# Measure.net
KiCad netlist of a schematic drawn in Altium Designer
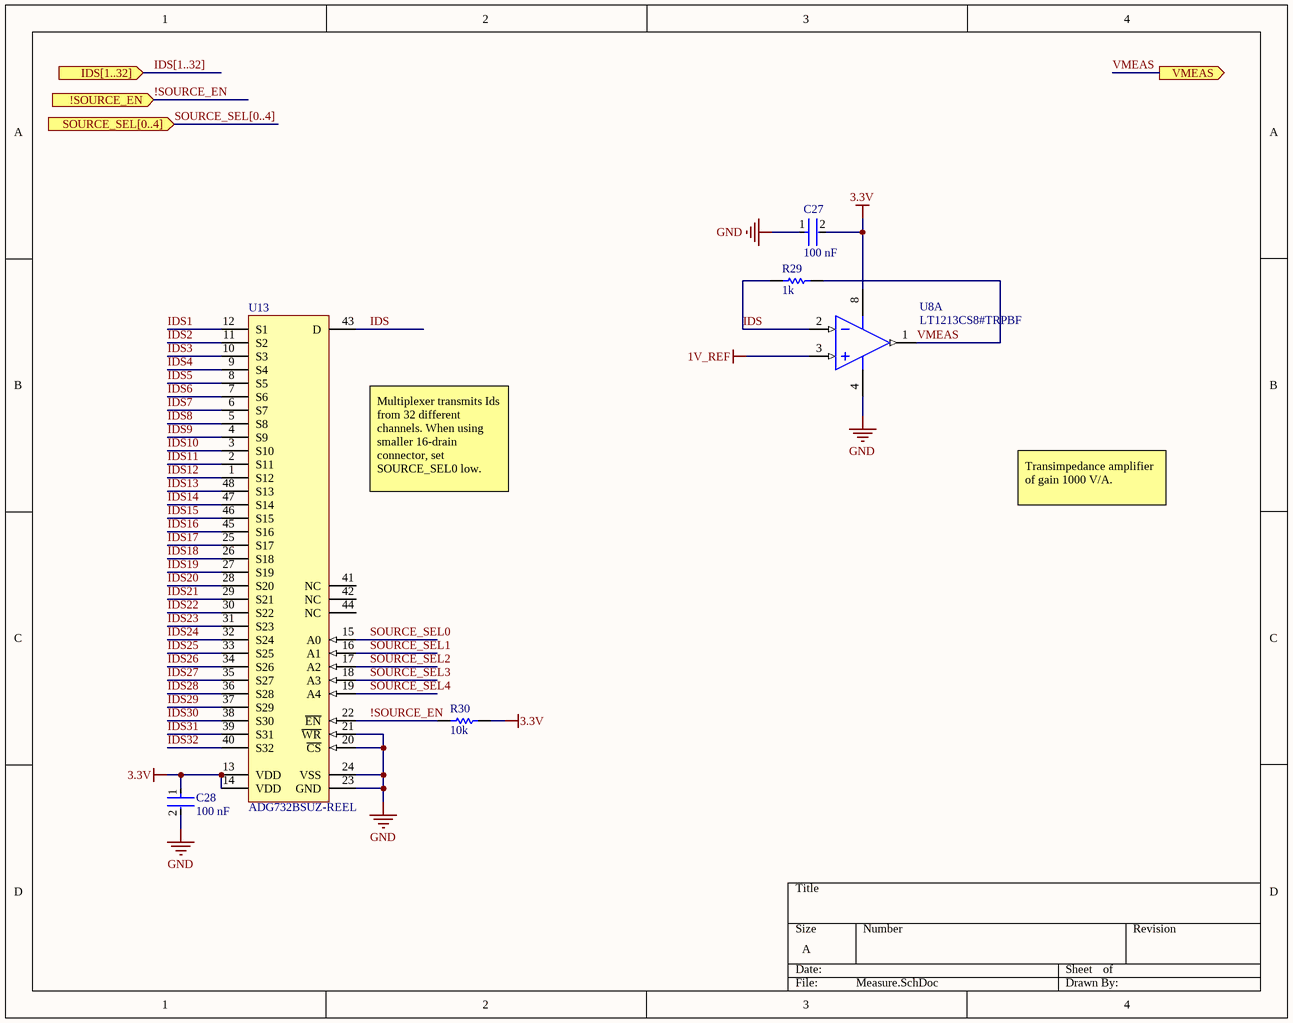
[diagram p0: Measure.SchDoc]

(export (version "E")
  (design (tool "Eeschema 10.0.6"))
  (components
    (comp (ref "C27")
      (value "100 nF")
      (footprint "FP-C0805C-DN-MFG")
      (description "CAP CER 0.1UF 50V X7R 0805")
      (fields
        (field (name "MANUFACTURER PART NUMBER") "C0805C104K5RACTU")
        (field (name "MANUFACTURER") "KEMET")
      )
      (libsource (lib "Altium Content Vault") (part "b4654b650e69147ec39a6b967a45e02"))
    )
    (comp (ref "C28")
      (value "100 nF")
      (footprint "FP-C0805C-DN-MFG")
      (description "CAP CER 0.1UF 50V X7R 0805")
      (fields
        (field (name "MANUFACTURER PART NUMBER") "C0805C104K5RACTU")
        (field (name "MANUFACTURER") "KEMET")
      )
      (libsource (lib "Altium Content Vault") (part "b4654b650e69147ec39a6b967a45e02"))
    )
    (comp (ref "R29")
      (value "1k")
      (footprint "RESC2013X55X40LL15T20")
      (description "TNPW08051K00BEEN")
      (fields (field (name "MANUFACTURER") "Vishay Dale"))
      (libsource (lib "Altium Content Vault") (part "RES"))
    )
    (comp (ref "R30")
      (value "10k")
      (footprint "RESC2013X60X35NL10T20")
      (description "Chip Resistor, 10 KOhm, +/- 1%, 0.125 W, -55 to 155 degC, 0805 (2012 Metric), RoHS, Tape and Reel")
      (fields (field (name "MANUFACTURER") "Yageo"))
      (libsource (lib "Altium Content Vault") (part "RES-2"))
    )
    (comp (ref "U8")
      (value "LT1213CS8#TRPBF")
      (footprint "LT-S8-8_N")
      (fields
        (field (name "LINEAR TECHNOLOGY PART NUMBER") "LT1213")
        (field (name "MANUFACTURER") "Linear Technology")
      )
      (libsource (lib "Altium Content Vault") (part "LT-LT1364-LT18XX-8"))
    )
    (comp (ref "U13")
      (value "ADG732BSUZ-REEL")
      (footprint "ADI-SU-48_N")
      (fields (field (name "MANUFACTURER") "Analog Devices"))
      (libsource (lib "Altium Content Vault") (part "ADI-ADG732-SU-48"))
    )
  )
  (nets
    (net (code "1") (name "/!SOURCE_EN") (class "Default")
      (node (ref "R30") (pin "2") (pinfunction "2_2") (pintype "passive"))
      (node (ref "U13") (pin "22") (pinfunction "~{EN}_22") (pintype "input"))
    )
    (net (code "2") (name "/IDS") (class "Default")
      (node (ref "R29") (pin "1") (pinfunction "1_1") (pintype "passive"))
      (node (ref "U13") (pin "43") (pinfunction "D_43") (pintype "passive"))
      (node (ref "U8") (pin "2") (pinfunction "-IN_A_2") (pintype "input"))
    )
    (net (code "3") (name "/IDS1") (class "Default")
      (node (ref "U13") (pin "12") (pinfunction "S1_12") (pintype "passive"))
    )
    (net (code "4") (name "/IDS2") (class "Default")
      (node (ref "U13") (pin "11") (pinfunction "S2_11") (pintype "passive"))
    )
    (net (code "5") (name "/IDS3") (class "Default")
      (node (ref "U13") (pin "10") (pinfunction "S3_10") (pintype "passive"))
    )
    (net (code "6") (name "/IDS4") (class "Default")
      (node (ref "U13") (pin "9") (pinfunction "S4_9") (pintype "passive"))
    )
    (net (code "7") (name "/IDS5") (class "Default")
      (node (ref "U13") (pin "8") (pinfunction "S5_8") (pintype "passive"))
    )
    (net (code "8") (name "/IDS6") (class "Default")
      (node (ref "U13") (pin "7") (pinfunction "S6_7") (pintype "passive"))
    )
    (net (code "9") (name "/IDS7") (class "Default")
      (node (ref "U13") (pin "6") (pinfunction "S7_6") (pintype "passive"))
    )
    (net (code "10") (name "/IDS8") (class "Default")
      (node (ref "U13") (pin "5") (pinfunction "S8_5") (pintype "passive"))
    )
    (net (code "11") (name "/IDS9") (class "Default")
      (node (ref "U13") (pin "4") (pinfunction "S9_4") (pintype "passive"))
    )
    (net (code "12") (name "/IDS10") (class "Default")
      (node (ref "U13") (pin "3") (pinfunction "S10_3") (pintype "passive"))
    )
    (net (code "13") (name "/IDS11") (class "Default")
      (node (ref "U13") (pin "2") (pinfunction "S11_2") (pintype "passive"))
    )
    (net (code "14") (name "/IDS12") (class "Default")
      (node (ref "U13") (pin "1") (pinfunction "S12_1") (pintype "passive"))
    )
    (net (code "15") (name "/IDS13") (class "Default")
      (node (ref "U13") (pin "48") (pinfunction "S13_48") (pintype "passive"))
    )
    (net (code "16") (name "/IDS14") (class "Default")
      (node (ref "U13") (pin "47") (pinfunction "S14_47") (pintype "passive"))
    )
    (net (code "17") (name "/IDS15") (class "Default")
      (node (ref "U13") (pin "46") (pinfunction "S15_46") (pintype "passive"))
    )
    (net (code "18") (name "/IDS16") (class "Default")
      (node (ref "U13") (pin "45") (pinfunction "S16_45") (pintype "passive"))
    )
    (net (code "19") (name "/IDS17") (class "Default")
      (node (ref "U13") (pin "25") (pinfunction "S17_25") (pintype "passive"))
    )
    (net (code "20") (name "/IDS18") (class "Default")
      (node (ref "U13") (pin "26") (pinfunction "S18_26") (pintype "passive"))
    )
    (net (code "21") (name "/IDS19") (class "Default")
      (node (ref "U13") (pin "27") (pinfunction "S19_27") (pintype "passive"))
    )
    (net (code "22") (name "/IDS20") (class "Default")
      (node (ref "U13") (pin "28") (pinfunction "S20_28") (pintype "passive"))
    )
    (net (code "23") (name "/IDS21") (class "Default")
      (node (ref "U13") (pin "29") (pinfunction "S21_29") (pintype "passive"))
    )
    (net (code "24") (name "/IDS22") (class "Default")
      (node (ref "U13") (pin "30") (pinfunction "S22_30") (pintype "passive"))
    )
    (net (code "25") (name "/IDS23") (class "Default")
      (node (ref "U13") (pin "31") (pinfunction "S23_31") (pintype "passive"))
    )
    (net (code "26") (name "/IDS24") (class "Default")
      (node (ref "U13") (pin "32") (pinfunction "S24_32") (pintype "passive"))
    )
    (net (code "27") (name "/IDS25") (class "Default")
      (node (ref "U13") (pin "33") (pinfunction "S25_33") (pintype "passive"))
    )
    (net (code "28") (name "/IDS26") (class "Default")
      (node (ref "U13") (pin "34") (pinfunction "S26_34") (pintype "passive"))
    )
    (net (code "29") (name "/IDS27") (class "Default")
      (node (ref "U13") (pin "35") (pinfunction "S27_35") (pintype "passive"))
    )
    (net (code "30") (name "/IDS28") (class "Default")
      (node (ref "U13") (pin "36") (pinfunction "S28_36") (pintype "passive"))
    )
    (net (code "31") (name "/IDS29") (class "Default")
      (node (ref "U13") (pin "37") (pinfunction "S29_37") (pintype "passive"))
    )
    (net (code "32") (name "/IDS30") (class "Default")
      (node (ref "U13") (pin "38") (pinfunction "S30_38") (pintype "passive"))
    )
    (net (code "33") (name "/IDS31") (class "Default")
      (node (ref "U13") (pin "39") (pinfunction "S31_39") (pintype "passive"))
    )
    (net (code "34") (name "/IDS32") (class "Default")
      (node (ref "U13") (pin "40") (pinfunction "S32_40") (pintype "passive"))
    )
    (net (code "36") (name "/SOURCE_SEL0") (class "Default")
      (node (ref "U13") (pin "15") (pinfunction "A0_15") (pintype "input"))
    )
    (net (code "37") (name "/SOURCE_SEL1") (class "Default")
      (node (ref "U13") (pin "16") (pinfunction "A1_16") (pintype "input"))
    )
    (net (code "38") (name "/SOURCE_SEL2") (class "Default")
      (node (ref "U13") (pin "17") (pinfunction "A2_17") (pintype "input"))
    )
    (net (code "39") (name "/SOURCE_SEL3") (class "Default")
      (node (ref "U13") (pin "18") (pinfunction "A3_18") (pintype "input"))
    )
    (net (code "40") (name "/SOURCE_SEL4") (class "Default")
      (node (ref "U13") (pin "19") (pinfunction "A4_19") (pintype "input"))
    )
    (net (code "42") (name "/VMEAS") (class "Default")
      (node (ref "R29") (pin "2") (pinfunction "2_2") (pintype "passive"))
      (node (ref "U8") (pin "1") (pinfunction "OUT_A_1") (pintype "output"))
    )
    (net (code "43") (name "1V_REF") (class "Default")
      (node (ref "U8") (pin "3") (pinfunction "+IN_A_3") (pintype "input"))
    )
    (net (code "44") (name "3.3V") (class "Default")
      (node (ref "C27") (pin "2") (pinfunction "2_2") (pintype "passive"))
      (node (ref "C28") (pin "1") (pinfunction "1_1") (pintype "passive"))
      (node (ref "R30") (pin "1") (pinfunction "1_1") (pintype "passive"))
      (node (ref "U13") (pin "13") (pinfunction "VDD_13") (pintype "power_in"))
      (node (ref "U13") (pin "14") (pinfunction "VDD_14") (pintype "power_in"))
      (node (ref "U8") (pin "8") (pinfunction "V+_8") (pintype "power_in"))
    )
    (net (code "45") (name "GND") (class "Default")
      (node (ref "C27") (pin "1") (pinfunction "1_1") (pintype "passive"))
      (node (ref "C28") (pin "2") (pinfunction "2_2") (pintype "passive"))
      (node (ref "U13") (pin "20") (pinfunction "~{CS}_20") (pintype "input"))
      (node (ref "U13") (pin "21") (pinfunction "~{WR}_21") (pintype "input"))
      (node (ref "U13") (pin "23") (pinfunction "GND_23") (pintype "power_in"))
      (node (ref "U13") (pin "24") (pinfunction "VSS_24") (pintype "power_in"))
      (node (ref "U8") (pin "4") (pinfunction "V-_4") (pintype "power_in"))
    )
    (net (code "46") (name "unconnected-(U13-NC-Pad41)") (class "Default")
      (node (ref "U13") (pin "41") (pinfunction "NC_41") (pintype "passive"))
    )
    (net (code "47") (name "unconnected-(U13-NC-Pad42)") (class "Default")
      (node (ref "U13") (pin "42") (pinfunction "NC_42") (pintype "passive"))
    )
    (net (code "48") (name "unconnected-(U13-NC-Pad44)") (class "Default")
      (node (ref "U13") (pin "44") (pinfunction "NC_44") (pintype "passive"))
    )
  )
)
